# SixAxR.net
KiCad netlist of a schematic drawn in Altium Designer
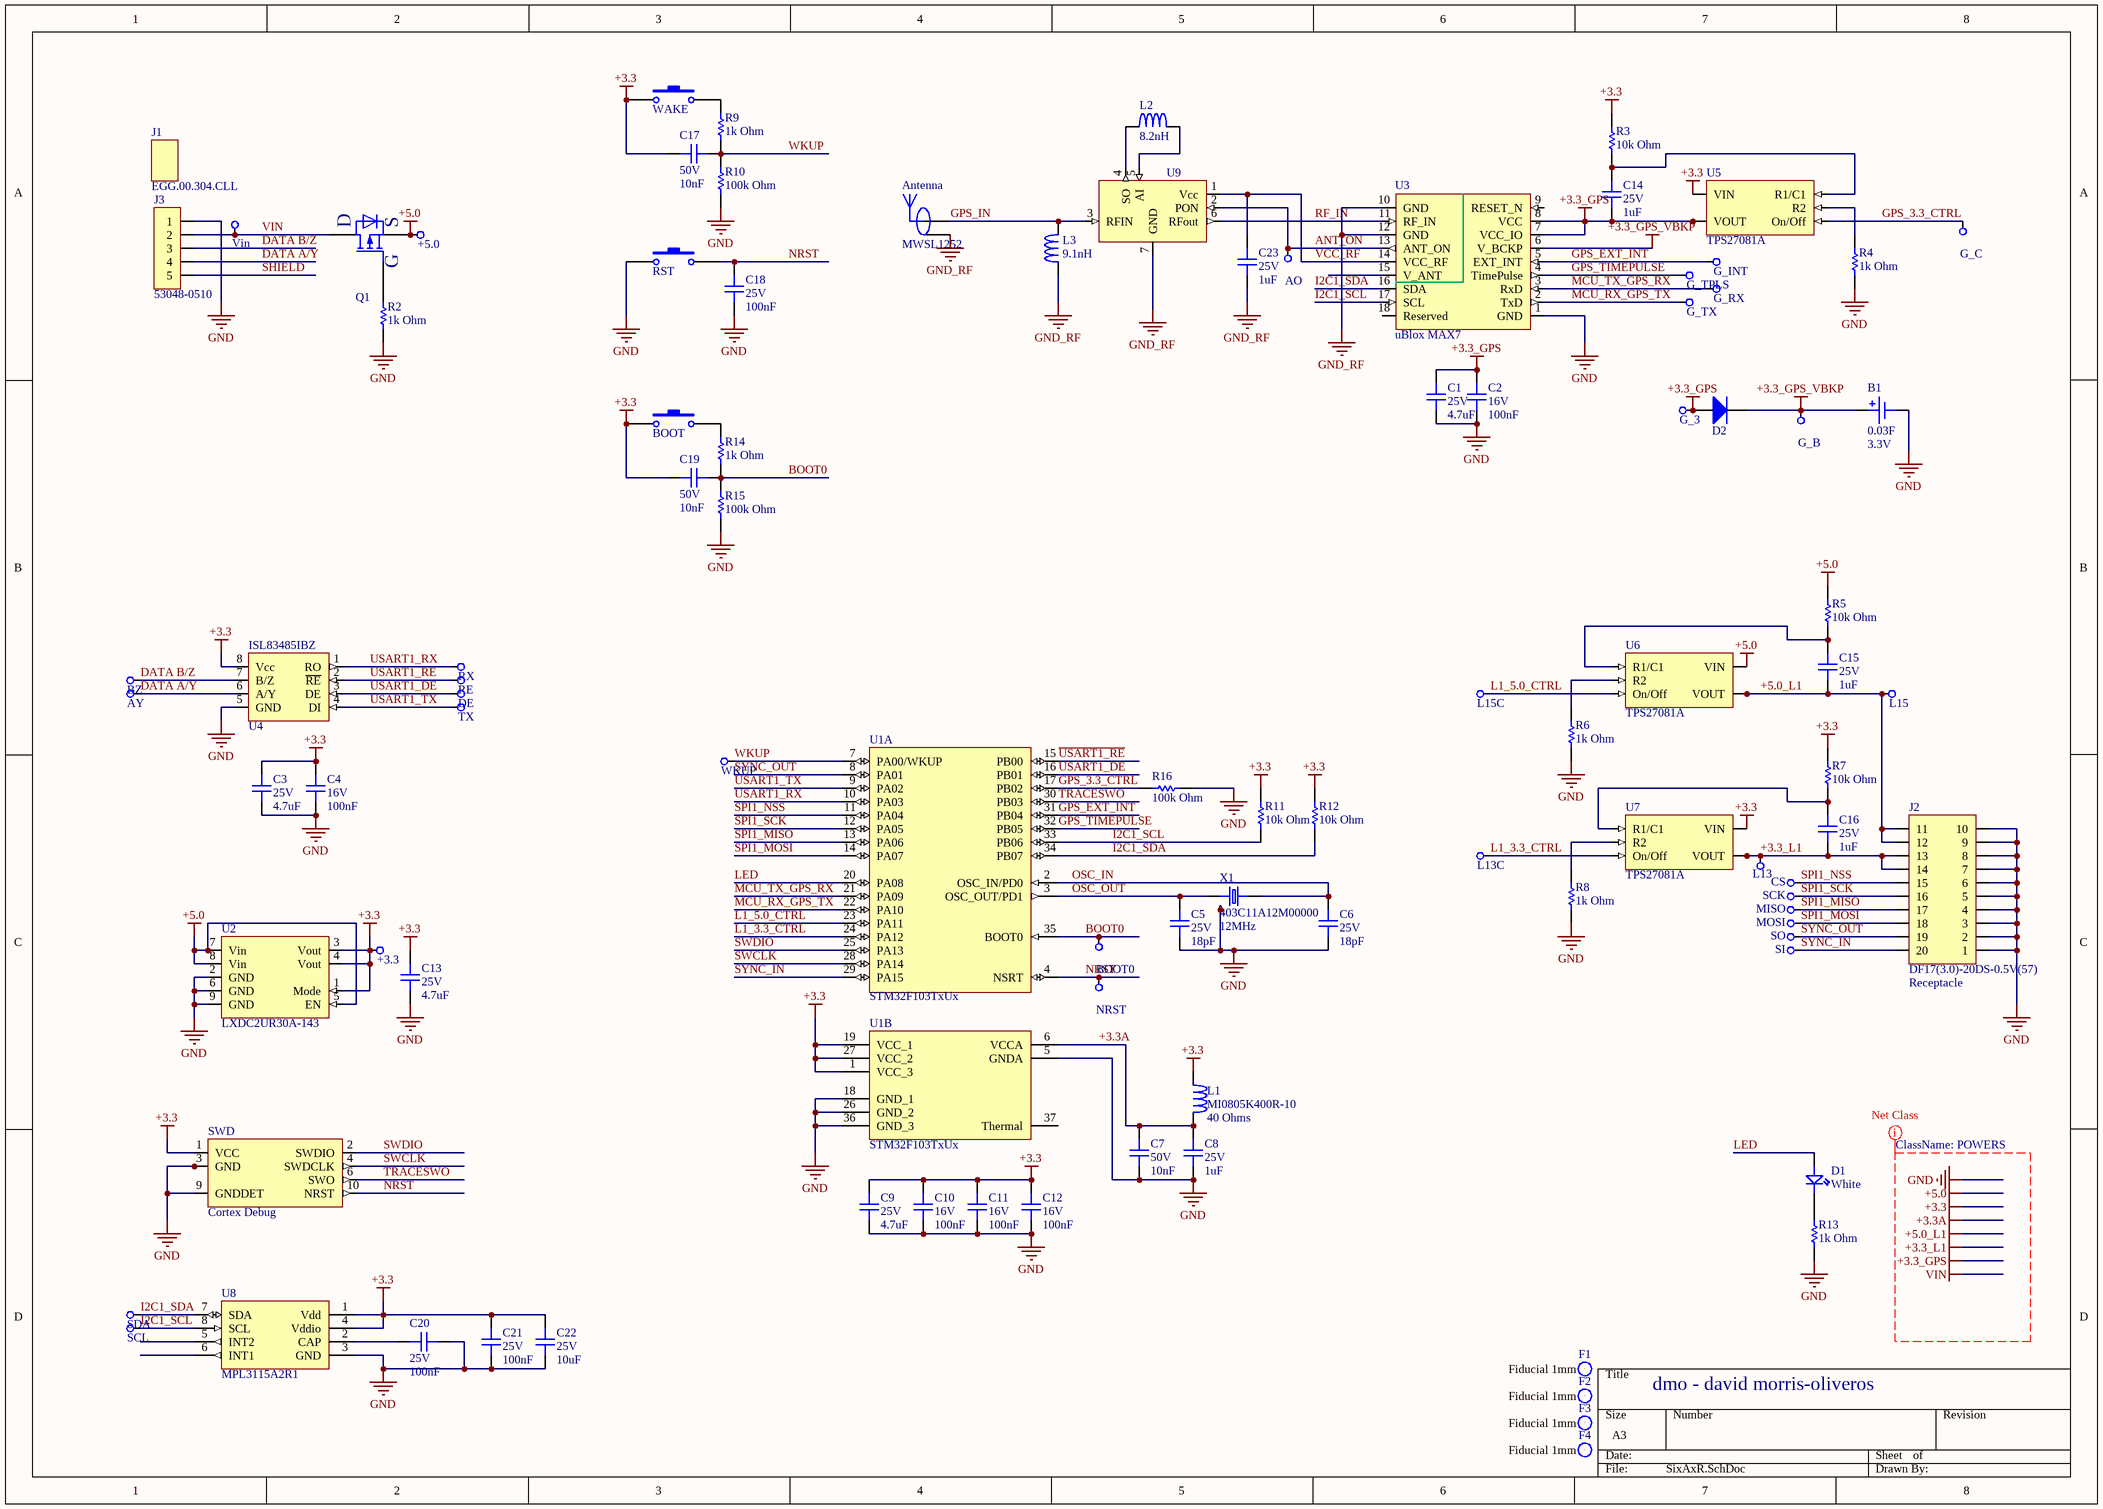
[diagram p0: SixAxR.SchDoc]

(export (version "E")
  (design (tool "Eeschema 10.0.6"))
  (components
    (comp (ref "+3.3")
      (value "TEST")
      (footprint "TEST_1.0mm, SMD")
      (libsource (lib "NaniBox_Conn") (part "TEST"))
    )
    (comp (ref "+5.0")
      (value "TEST")
      (footprint "TEST_1.0mm, SMD")
      (libsource (lib "NaniBox_Conn") (part "TEST"))
    )
    (comp (ref "Antenna")
      (value "MWSL1252")
      (footprint "MWSL1252 - Vertical - SMALLER")
      (description "GPS Antenna, Passive, SMD")
      (fields (field (name "MANUFACTURER") "Maruwa"))
      (libsource (lib "NaniBox_Conn") (part "MWSL1252"))
    )
    (comp (ref "AO")
      (value "TEST")
      (footprint "TEST_0.5mm, SMD")
      (libsource (lib "NaniBox_Conn") (part "TEST"))
    )
    (comp (ref "AY")
      (value "TEST")
      (footprint "TEST_0.5mm, SMD")
      (libsource (lib "NaniBox_Conn") (part "TEST"))
    )
    (comp (ref "B1")
      (value "0.03F")
      (footprint "PAS409HR-VE5R")
      (description "Super Cap, 3.3V, 0.03F")
      (fields
        (field (name "MANUFACTURER") "Taiyo Yuden")
        (field (name "MANUFACTURER PART NUMBER") "PAS409HR-VE5R")
        (field (name "VOLTAGE") "3.3V")
      )
      (libsource (lib "NaniBox") (part "PAS409HR-VE5R"))
    )
    (comp (ref "BOOT")
      (value "TL1015AF160QG")
      (footprint "TL1015AF160QG")
      (description "Switch, Tactile, SMD")
      (fields (field (name "MANUFACTURER") "E-Switch"))
      (libsource (lib "NaniBox") (part "TL1015AF160QG"))
    )
    (comp (ref "BOOT0")
      (value "TEST")
      (footprint "TEST_0.5mm, SMD")
      (libsource (lib "NaniBox_Conn") (part "TEST"))
    )
    (comp (ref "BZ")
      (value "TEST")
      (footprint "TEST_0.5mm, SMD")
      (libsource (lib "NaniBox_Conn") (part "TEST"))
    )
    (comp (ref "C1")
      (value "4.7uF")
      (footprint "CAP 0805")
      (description "MLCC, 4.7uF, 0805, 10%, 25V, X5R")
      (fields
        (field (name "MANUFACTURER") "Samsung")
        (field (name "MANUFACTURER PART NUMBER") "CL21A475KAQNNNE")
        (field (name "VOLTAGE RATING") "25V")
      )
      (libsource (lib "NaniBox") (part "CL21A475KAQNNNE"))
    )
    (comp (ref "C2")
      (value "100nF")
      (footprint "CAP 0402")
      (description "MLCC, 100nF, 0402, 10%, 16V, X7R")
      (fields
        (field (name "MANUFACTURER") "Samsung")
        (field (name "MANUFACTURER PART NUMBER") "CL05B104KO5NNNC")
        (field (name "VOLTAGE RATING") "16V")
      )
      (libsource (lib "NaniBox") (part "CL05B104KO5NNNC"))
    )
    (comp (ref "C3")
      (value "4.7uF")
      (footprint "CAP 0805")
      (description "MLCC, 4.7uF, 0805, 10%, 25V, X5R")
      (fields
        (field (name "MANUFACTURER") "Samsung")
        (field (name "MANUFACTURER PART NUMBER") "CL21A475KAQNNNE")
        (field (name "VOLTAGE RATING") "25V")
      )
      (libsource (lib "NaniBox") (part "CL21A475KAQNNNE"))
    )
    (comp (ref "C4")
      (value "100nF")
      (footprint "CAP 0402")
      (description "MLCC, 100nF, 0402, 10%, 16V, X7R")
      (fields
        (field (name "MANUFACTURER") "Samsung")
        (field (name "MANUFACTURER PART NUMBER") "CL05B104KO5NNNC")
        (field (name "VOLTAGE RATING") "16V")
      )
      (libsource (lib "NaniBox") (part "CL05B104KO5NNNC"))
    )
    (comp (ref "C5")
      (value "18pF")
      (footprint "CAP 0402")
      (description "MLCC, 18pF, 0402, 5%, 25V, C0G")
      (fields
        (field (name "MANUFACTURER") "muRata")
        (field (name "MANUFACTURER PART NUMBER") "GRM1555C1E180JA01D")
        (field (name "VOLTAGE RATING") "25V")
      )
      (libsource (lib "NaniBox") (part "GRM1555C1E180JA01D"))
    )
    (comp (ref "C6")
      (value "18pF")
      (footprint "CAP 0402")
      (description "MLCC, 18pF, 0402, 5%, 25V, C0G")
      (fields
        (field (name "MANUFACTURER") "muRata")
        (field (name "MANUFACTURER PART NUMBER") "GRM1555C1E180JA01D")
        (field (name "VOLTAGE RATING") "25V")
      )
      (libsource (lib "NaniBox") (part "GRM1555C1E180JA01D"))
    )
    (comp (ref "C7")
      (value "10nF")
      (footprint "CAP 0402")
      (description "MLCC, 10nF, 0402, 10%, 50V, X7R")
      (fields
        (field (name "MANUFACTURER") "Samsung")
        (field (name "MANUFACTURER PART NUMBER") "CL05B103KB5NNNC")
        (field (name "VOLTAGE RATING") "50V")
      )
      (libsource (lib "NaniBox") (part "CL05B103KB5NNNC"))
    )
    (comp (ref "C8")
      (value "1uF")
      (footprint "CAP 0603")
      (description "MLCC, 1uF, 0603, 10%, 25V")
      (fields
        (field (name "MANUFACTURER") "Taiyo Yuden")
        (field (name "MANUFACTURER PART NUMBER") "TMK107B7105KA-T")
        (field (name "VOLTAGE RATING") "25V")
      )
      (libsource (lib "NaniBox") (part "TMK107B7105KA-T"))
    )
    (comp (ref "C9")
      (value "4.7uF")
      (footprint "CAP 0805")
      (description "MLCC, 4.7uF, 0805, 10%, 25V, X5R")
      (fields
        (field (name "MANUFACTURER") "Samsung")
        (field (name "MANUFACTURER PART NUMBER") "CL21A475KAQNNNE")
        (field (name "VOLTAGE RATING") "25V")
      )
      (libsource (lib "NaniBox") (part "CL21A475KAQNNNE"))
    )
    (comp (ref "C10")
      (value "100nF")
      (footprint "CAP 0402")
      (description "MLCC, 100nF, 0402, 10%, 16V, X7R")
      (fields
        (field (name "MANUFACTURER") "Samsung")
        (field (name "MANUFACTURER PART NUMBER") "CL05B104KO5NNNC")
        (field (name "VOLTAGE RATING") "16V")
      )
      (libsource (lib "NaniBox") (part "CL05B104KO5NNNC"))
    )
    (comp (ref "C11")
      (value "100nF")
      (footprint "CAP 0402")
      (description "MLCC, 100nF, 0402, 10%, 16V, X7R")
      (fields
        (field (name "MANUFACTURER") "Samsung")
        (field (name "MANUFACTURER PART NUMBER") "CL05B104KO5NNNC")
        (field (name "VOLTAGE RATING") "16V")
      )
      (libsource (lib "NaniBox") (part "CL05B104KO5NNNC"))
    )
    (comp (ref "C12")
      (value "100nF")
      (footprint "CAP 0402")
      (description "MLCC, 100nF, 0402, 10%, 16V, X7R")
      (fields
        (field (name "MANUFACTURER") "Samsung")
        (field (name "MANUFACTURER PART NUMBER") "CL05B104KO5NNNC")
        (field (name "VOLTAGE RATING") "16V")
      )
      (libsource (lib "NaniBox") (part "CL05B104KO5NNNC"))
    )
    (comp (ref "C13")
      (value "4.7uF")
      (footprint "CAP 0805")
      (description "MLCC, 4.7uF, 0805, 10%, 25V, X5R")
      (fields
        (field (name "MANUFACTURER") "Samsung")
        (field (name "MANUFACTURER PART NUMBER") "CL21A475KAQNNNE")
        (field (name "VOLTAGE RATING") "25V")
      )
      (libsource (lib "NaniBox") (part "CL21A475KAQNNNE"))
    )
    (comp (ref "C14")
      (value "1uF")
      (footprint "CAP 0603")
      (description "MLCC, 1uF, 0603, 10%, 25V, X5R")
      (fields
        (field (name "MANUFACTURER") "Samsung")
        (field (name "MANUFACTURER PART NUMBER") "CL10A105KA8NNNC")
        (field (name "VOLTAGE RATING") "25V")
      )
      (libsource (lib "NaniBox") (part "CL10A105KA8NNNC"))
    )
    (comp (ref "C15")
      (value "1uF")
      (footprint "CAP 0603")
      (description "MLCC, 1uF, 0603, 10%, 25V, X5R")
      (fields
        (field (name "MANUFACTURER") "Samsung")
        (field (name "MANUFACTURER PART NUMBER") "CL10A105KA8NNNC")
        (field (name "VOLTAGE RATING") "25V")
      )
      (libsource (lib "NaniBox") (part "CL10A105KA8NNNC"))
    )
    (comp (ref "C16")
      (value "1uF")
      (footprint "CAP 0603")
      (description "MLCC, 1uF, 0603, 10%, 25V, X5R")
      (fields
        (field (name "MANUFACTURER") "Samsung")
        (field (name "MANUFACTURER PART NUMBER") "CL10A105KA8NNNC")
        (field (name "VOLTAGE RATING") "25V")
      )
      (libsource (lib "NaniBox") (part "CL10A105KA8NNNC"))
    )
    (comp (ref "C17")
      (value "10nF")
      (footprint "CAP 0402")
      (description "MLCC, 10nF, 0402, 10%, 50V, X7R")
      (fields
        (field (name "MANUFACTURER") "Samsung")
        (field (name "MANUFACTURER PART NUMBER") "CL05B103KB5NNNC")
        (field (name "VOLTAGE RATING") "50V")
      )
      (libsource (lib "NaniBox") (part "CL05B103KB5NNNC"))
    )
    (comp (ref "C18")
      (value "100nF")
      (footprint "CAP 0402")
      (description "MLCC, 100nF, 0402, 10%, 25V, X5R")
      (fields
        (field (name "MANUFACTURER") "Samsung")
        (field (name "MANUFACTURER PART NUMBER") "CL05A104KA5NNNC")
        (field (name "VOLTAGE RATING") "25V")
      )
      (libsource (lib "NaniBox") (part "CL05A104KA5NNNC"))
    )
    (comp (ref "C19")
      (value "10nF")
      (footprint "CAP 0402")
      (description "MLCC, 10nF, 0402, 10%, 50V, X7R")
      (fields
        (field (name "MANUFACTURER") "Samsung")
        (field (name "MANUFACTURER PART NUMBER") "CL05B103KB5NNNC")
        (field (name "VOLTAGE RATING") "50V")
      )
      (libsource (lib "NaniBox") (part "CL05B103KB5NNNC"))
    )
    (comp (ref "C20")
      (value "100nF")
      (footprint "CAP 0402")
      (description "MLCC, 100nF, 0402, 10%, 25V, X5R")
      (fields
        (field (name "MANUFACTURER") "Samsung")
        (field (name "MANUFACTURER PART NUMBER") "CL05A104KA5NNNC")
        (field (name "VOLTAGE RATING") "25V")
      )
      (libsource (lib "NaniBox") (part "CL05A104KA5NNNC"))
    )
    (comp (ref "C21")
      (value "100nF")
      (footprint "CAP 0402")
      (description "MLCC, 100nF, 0402, 10%, 25V, X5R")
      (fields
        (field (name "MANUFACTURER") "Samsung")
        (field (name "MANUFACTURER PART NUMBER") "CL05A104KA5NNNC")
        (field (name "VOLTAGE RATING") "25V")
      )
      (libsource (lib "NaniBox") (part "CL05A104KA5NNNC"))
    )
    (comp (ref "C22")
      (value "10uF")
      (footprint "CAP 0805")
      (description "MLCC, 10uF, 0805, 10%, 25V, X5R")
      (fields
        (field (name "MANUFACTURER") "Samsung")
        (field (name "MANUFACTURER PART NUMBER") "CL21A106KAYNNNE")
        (field (name "VOLTAGE RATING") "25V")
      )
      (libsource (lib "NaniBox") (part "CL21A106KAYNNNE"))
    )
    (comp (ref "C23")
      (value "1uF")
      (footprint "CAP 0603")
      (description "MLCC, 1uF, 0603, 10%, 25V, X5R")
      (fields
        (field (name "MANUFACTURER") "Samsung")
        (field (name "MANUFACTURER PART NUMBER") "CL10A105KA8NNNC")
        (field (name "VOLTAGE RATING") "25V")
      )
      (libsource (lib "NaniBox") (part "CL10A105KA8NNNC"))
    )
    (comp (ref "CS")
      (value "TEST")
      (footprint "TEST_0.5mm, SMD")
      (libsource (lib "NaniBox_Conn") (part "TEST"))
    )
    (comp (ref "D1")
      (value "White")
      (footprint "LED 0603")
      (description "LED, White, 0603")
      (fields (field (name "MANUFACTURER PART NUMBER") "1608SWD-04"))
      (libsource (lib "NaniBox") (part "1608SWD-04"))
    )
    (comp (ref "D2")
      (value "CDSQR400B")
      (footprint "SOD-923F")
      (description "DIODE, Switching, Low Leakage, 90V, 100mA")
      (fields (field (name "MANUFACTURER") "Comchip Technology"))
      (libsource (lib "NaniBox") (part "CDSQR400B"))
    )
    (comp (ref "DE")
      (value "TEST")
      (footprint "TEST_0.5mm, SMD")
      (libsource (lib "NaniBox_Conn") (part "TEST"))
    )
    (comp (ref "F1")
      (value "~")
      (footprint "Fiducial_1mm")
      (libsource (lib "NaniBox_Conn") (part "Fiducial 1mm"))
    )
    (comp (ref "F2")
      (value "~")
      (footprint "Fiducial_1mm")
      (libsource (lib "NaniBox_Conn") (part "Fiducial 1mm"))
    )
    (comp (ref "F3")
      (value "~")
      (footprint "Fiducial_1mm")
      (libsource (lib "NaniBox_Conn") (part "Fiducial 1mm"))
    )
    (comp (ref "F4")
      (value "~")
      (footprint "Fiducial_1mm")
      (libsource (lib "NaniBox_Conn") (part "Fiducial 1mm"))
    )
    (comp (ref "G_3")
      (value "TEST")
      (footprint "TEST_0.5mm, SMD")
      (libsource (lib "NaniBox_Conn") (part "TEST"))
    )
    (comp (ref "G_B")
      (value "TEST")
      (footprint "TEST_0.5mm, SMD")
      (libsource (lib "NaniBox_Conn") (part "TEST"))
    )
    (comp (ref "G_C")
      (value "TEST")
      (footprint "TEST_0.5mm, SMD")
      (libsource (lib "NaniBox_Conn") (part "TEST"))
    )
    (comp (ref "G_INT")
      (value "TEST")
      (footprint "TEST_0.5mm, SMD")
      (libsource (lib "NaniBox_Conn") (part "TEST"))
    )
    (comp (ref "G_RX")
      (value "TEST")
      (footprint "TEST_0.5mm, SMD")
      (libsource (lib "NaniBox_Conn") (part "TEST"))
    )
    (comp (ref "G_TPLS")
      (value "TEST")
      (footprint "TEST_0.5mm, SMD")
      (libsource (lib "NaniBox_Conn") (part "TEST"))
    )
    (comp (ref "G_TX")
      (value "TEST")
      (footprint "TEST_0.5mm, SMD")
      (libsource (lib "NaniBox_Conn") (part "TEST"))
    )
    (comp (ref "J1")
      (value "EGG.00.304.CLL")
      (footprint "EGG.00.304.CLL")
      (description "LEMO 00, 4-pin")
      (libsource (lib "NaniBox") (part "EGG.00.304.CLL"))
    )
    (comp (ref "J2")
      (value "DF17(3.0)-20DS-0.5V(57)")
      (footprint "DF17(3.0)-20DS-0.5V(57)")
      (description "Conn, B2B, 20 Pos, RCPT")
      (fields (field (name "MANUFACTURER") "Hirose") (field (name "TYPE") "Receptacle"))
      (libsource (lib "NaniBox") (part "DF17(3.0)-20DS-0.5V(57)"))
    )
    (comp (ref "J3")
      (value "53048-0510")
      (footprint "PicoBlade, 53048-0510")
      (description "PicoBlade, Header, R/A, PTH, 5 Pos, 1.25mm Pitch")
      (fields (field (name "MANUFACTURER") "Molex"))
      (libsource (lib "NaniBox_Conn") (part "53048-0510"))
    )
    (comp (ref "L1")
      (value "MI0805K400R-10")
      (footprint "IND 0805")
      (description "IND, EMI, 40Ohm, 100MHz, 1.5A, 0805")
      (fields (field (name "MANUFACTURER") "Laird") (field (name "IMPEDENCE") "40 Ohms"))
      (libsource (lib "NaniBox") (part "MI0805K400R-10"))
    )
    (comp (ref "L2")
      (value "8.2nH")
      (footprint "IND 0402")
      (description "IND, 8.2nH, 5%, 100MHz")
      (fields
        (field (name "MANUFACTURER") "Murata Electronics")
        (field (name "MANUFACTURER PART NUMBER") "LQW15AN8N2J00D")
      )
      (libsource (lib "NaniBox") (part "LQW15AN8N2J00D"))
    )
    (comp (ref "L3")
      (value "9.1nH")
      (footprint "IND 0402")
      (description "IND, 9.1nH, 5%, 100MHz")
      (fields
        (field (name "MANUFACTURER") "Murata Electronics")
        (field (name "MANUFACTURER PART NUMBER") "LQW15AN9N1J00D")
      )
      (libsource (lib "NaniBox") (part "LQW15AN9N1J00D"))
    )
    (comp (ref "L13")
      (value "TEST")
      (footprint "TEST_0.5mm, SMD")
      (libsource (lib "NaniBox_Conn") (part "TEST"))
    )
    (comp (ref "L13C")
      (value "TEST")
      (footprint "TEST_0.5mm, SMD")
      (libsource (lib "NaniBox_Conn") (part "TEST"))
    )
    (comp (ref "L15")
      (value "TEST")
      (footprint "TEST_0.5mm, SMD")
      (libsource (lib "NaniBox_Conn") (part "TEST"))
    )
    (comp (ref "L15C")
      (value "TEST")
      (footprint "TEST_0.5mm, SMD")
      (libsource (lib "NaniBox_Conn") (part "TEST"))
    )
    (comp (ref "MISO")
      (value "TEST")
      (footprint "TEST_0.5mm, SMD")
      (libsource (lib "NaniBox_Conn") (part "TEST"))
    )
    (comp (ref "MOSI")
      (value "TEST")
      (footprint "TEST_0.5mm, SMD")
      (libsource (lib "NaniBox_Conn") (part "TEST"))
    )
    (comp (ref "NRST")
      (value "TEST")
      (footprint "TEST_0.5mm, SMD")
      (libsource (lib "NaniBox_Conn") (part "TEST"))
    )
    (comp (ref "Q1")
      (value "PMV48XP,215")
      (footprint "SOT23-3")
      (description "MOSFET P-CH -20 V -3.5 A, SOT23-3")
      (fields (field (name "MANUFACTURER") "NXP"))
      (libsource (lib "NaniBox") (part "PMV48XP,215"))
    )
    (comp (ref "R2")
      (value "1k Ohm")
      (footprint "RES 0402")
      (description "RES, 0402, 1k, 1%")
      (fields (field (name "TOLERANCE") "1%") (field (name "MANUFACTURER") "Yageo"))
      (libsource (lib "NaniBox") (part "P311-1.00KLRTR-ND"))
    )
    (comp (ref "R3")
      (value "10k Ohm")
      (footprint "RES 0402")
      (description "RES, 0402, 10k, 1%")
      (fields (field (name "TOLERANCE") "1%") (field (name "MANUFACTURER") "Yageo"))
      (libsource (lib "NaniBox") (part "P311-10.0KLRTR-ND"))
    )
    (comp (ref "R4")
      (value "1k Ohm")
      (footprint "RES 0402")
      (description "RES, 0402, 1k, 1%")
      (fields (field (name "TOLERANCE") "1%") (field (name "MANUFACTURER") "Yageo"))
      (libsource (lib "NaniBox") (part "P311-1.00KLRTR-ND"))
    )
    (comp (ref "R5")
      (value "10k Ohm")
      (footprint "RES 0402")
      (description "RES, 0402, 10k, 1%")
      (fields (field (name "TOLERANCE") "1%") (field (name "MANUFACTURER") "Yageo"))
      (libsource (lib "NaniBox") (part "P311-10.0KLRTR-ND"))
    )
    (comp (ref "R6")
      (value "1k Ohm")
      (footprint "RES 0402")
      (description "RES, 0402, 1k, 1%")
      (fields (field (name "TOLERANCE") "1%") (field (name "MANUFACTURER") "Yageo"))
      (libsource (lib "NaniBox") (part "P311-1.00KLRTR-ND"))
    )
    (comp (ref "R7")
      (value "10k Ohm")
      (footprint "RES 0402")
      (description "RES, 0402, 10k, 1%")
      (fields (field (name "TOLERANCE") "1%") (field (name "MANUFACTURER") "Yageo"))
      (libsource (lib "NaniBox") (part "P311-10.0KLRTR-ND"))
    )
    (comp (ref "R8")
      (value "1k Ohm")
      (footprint "RES 0402")
      (description "RES, 0402, 1k, 1%")
      (fields (field (name "TOLERANCE") "1%") (field (name "MANUFACTURER") "Yageo"))
      (libsource (lib "NaniBox") (part "P311-1.00KLRTR-ND"))
    )
    (comp (ref "R9")
      (value "1k Ohm")
      (footprint "RES 0402")
      (description "RES, 0402, 1k, 1%")
      (fields (field (name "TOLERANCE") "1%") (field (name "MANUFACTURER") "Yageo"))
      (libsource (lib "NaniBox") (part "P311-1.00KLRTR-ND"))
    )
    (comp (ref "R10")
      (value "100k Ohm")
      (footprint "RES 0402")
      (description "RES, 0402, 100k, 1%")
      (fields (field (name "TOLERANCE") "1%") (field (name "MANUFACTURER") "Yageo"))
      (libsource (lib "NaniBox") (part "P311-100KLRTR-ND"))
    )
    (comp (ref "R11")
      (value "10k Ohm")
      (footprint "RES 0402")
      (description "RES, 0402, 10k, 1%")
      (fields (field (name "TOLERANCE") "1%") (field (name "MANUFACTURER") "Yageo"))
      (libsource (lib "NaniBox") (part "P311-10.0KLRTR-ND"))
    )
    (comp (ref "R12")
      (value "10k Ohm")
      (footprint "RES 0402")
      (description "RES, 0402, 10k, 1%")
      (fields (field (name "TOLERANCE") "1%") (field (name "MANUFACTURER") "Yageo"))
      (libsource (lib "NaniBox") (part "P311-10.0KLRTR-ND"))
    )
    (comp (ref "R13")
      (value "1k Ohm")
      (footprint "RES 0402")
      (description "RES, 0402, 1k, 1%")
      (fields (field (name "TOLERANCE") "1%") (field (name "MANUFACTURER") "Yageo"))
      (libsource (lib "NaniBox") (part "P311-1.00KLRTR-ND"))
    )
    (comp (ref "R14")
      (value "1k Ohm")
      (footprint "RES 0402")
      (description "RES, 0402, 1k, 1%")
      (fields (field (name "TOLERANCE") "1%") (field (name "MANUFACTURER") "Yageo"))
      (libsource (lib "NaniBox") (part "P311-1.00KLRTR-ND"))
    )
    (comp (ref "R15")
      (value "100k Ohm")
      (footprint "RES 0402")
      (description "RES, 0402, 100k, 1%")
      (fields (field (name "TOLERANCE") "1%") (field (name "MANUFACTURER") "Yageo"))
      (libsource (lib "NaniBox") (part "P311-100KLRTR-ND"))
    )
    (comp (ref "R16")
      (value "100k Ohm")
      (footprint "RES 0402")
      (description "RES, 0402, 100k, 1%")
      (fields (field (name "TOLERANCE") "1%") (field (name "MANUFACTURER") "Yageo"))
      (libsource (lib "NaniBox") (part "P311-100KLRTR-ND"))
    )
    (comp (ref "RE")
      (value "TEST")
      (footprint "TEST_0.5mm, SMD")
      (libsource (lib "NaniBox_Conn") (part "TEST"))
    )
    (comp (ref "RST")
      (value "TL1015AF160QG")
      (footprint "TL1015AF160QG")
      (description "Switch, Tactile, SMD")
      (fields (field (name "MANUFACTURER") "E-Switch"))
      (libsource (lib "NaniBox") (part "TL1015AF160QG"))
    )
    (comp (ref "RX")
      (value "TEST")
      (footprint "TEST_0.5mm, SMD")
      (libsource (lib "NaniBox_Conn") (part "TEST"))
    )
    (comp (ref "SCK")
      (value "TEST")
      (footprint "TEST_0.5mm, SMD")
      (libsource (lib "NaniBox_Conn") (part "TEST"))
    )
    (comp (ref "SCL")
      (value "TEST")
      (footprint "TEST_0.5mm, SMD")
      (libsource (lib "NaniBox_Conn") (part "TEST"))
    )
    (comp (ref "SDA")
      (value "TEST")
      (footprint "TEST_0.5mm, SMD")
      (libsource (lib "NaniBox_Conn") (part "TEST"))
    )
    (comp (ref "SI")
      (value "TEST")
      (footprint "TEST_0.5mm, SMD")
      (libsource (lib "NaniBox_Conn") (part "TEST"))
    )
    (comp (ref "SO")
      (value "TEST")
      (footprint "TEST_0.5mm, SMD")
      (libsource (lib "NaniBox_Conn") (part "TEST"))
    )
    (comp (ref "SWD")
      (value "CORTEX_DEBUG")
      (footprint "H_05x02 - 1.27mm")
      (description "Cortex Debug")
      (fields (field (name "MANUFACTURER PART NUMBER") "Cortex Debug"))
      (libsource (lib "NaniBox") (part "CORTEX_DEBUG"))
    )
    (comp (ref "TX")
      (value "TEST")
      (footprint "TEST_0.5mm, SMD")
      (libsource (lib "NaniBox_Conn") (part "TEST"))
    )
    (comp (ref "U1")
      (value "STM32F103TxUx")
      (footprint "QFN36 - 0.5mm - NO THERMAL VIAS")
      (description "MCU, ARM-based 32-bit MCU with 64  or 128 KB Flash, USB, CAN, 7 timers, 2 ADCs, 9 com. interfaces")
      (libsource (lib "NaniBox") (part "STM32F103TxUx"))
    )
    (comp (ref "U2")
      (value "LXDC2UR30A-143")
      (footprint "BGA - 9 - LXDC2UR")
      (description "DC-DC 3.0Vout 600mA 2.5x2.3mm uDCDC")
      (libsource (lib "NaniBox") (part "LXDC2UR30A-143"))
    )
    (comp (ref "U3")
      (value "uBlox MAX7")
      (footprint "uBlox MAX7")
      (description "GPS, u-blox 7 GPS/GNSS module")
      (libsource (lib "NaniBox") (part "uBlox MAX7"))
    )
    (comp (ref "U4")
      (value "ISL83485IBZ")
      (footprint "SOIC8")
      (description "RS-422/RS-485, 3.3V, HalfDuplex, TRN 1TX/1RX, W/SHTDN")
      (fields (field (name "MANUFACTURER") "Intersil"))
      (libsource (lib "NaniBox") (part "ISL83485IBZ"))
    )
    (comp (ref "U5")
      (value "TPS27081ADDCR")
      (footprint "SOT23-6")
      (description "High Side Load Switch PFET 1.2V-8V 3A")
      (fields
        (field (name "MANUFACTURER") "TI")
        (field (name "MANUFACTURER PART NUMBER - SIMPLE") "TPS27081A")
      )
      (libsource (lib "") (part "TPS27081ADDCR_1"))
    )
    (comp (ref "U6")
      (value "TPS27081ADDCR")
      (footprint "SOT23-6")
      (description "High Side Load Switch PFET 1.2V-8V 3A")
      (fields
        (field (name "MANUFACTURER") "TI")
        (field (name "MANUFACTURER PART NUMBER - SIMPLE") "TPS27081A")
      )
      (libsource (lib "NaniBox") (part "TPS27081ADDCR"))
    )
    (comp (ref "U7")
      (value "TPS27081ADDCR")
      (footprint "SOT23-6")
      (description "High Side Load Switch PFET 1.2V-8V 3A")
      (fields
        (field (name "MANUFACTURER") "TI")
        (field (name "MANUFACTURER PART NUMBER - SIMPLE") "TPS27081A")
      )
      (libsource (lib "NaniBox") (part "TPS27081ADDCR"))
    )
    (comp (ref "U8")
      (value "MPL3115A2R1")
      (footprint "MPL3115A2R1")
      (description "Barometric Pressure Sensor, SMD")
      (fields (field (name "MANUFACTURER") "Freescale"))
      (libsource (lib "NaniBox") (part "MPL3115A2R1"))
    )
    (comp (ref "U9")
      (value "BGM1043N7")
      (footprint "TSNP-7-10")
      (description "RF, LNA, GPS")
      (fields (field (name "MANUFACTURER") "Infineon"))
      (libsource (lib "NaniBox") (part "BGM1043N7"))
    )
    (comp (ref "Vin")
      (value "TEST")
      (footprint "TEST_1.0mm, SMD")
      (libsource (lib "NaniBox_Conn") (part "TEST"))
    )
    (comp (ref "WAKE")
      (value "EVQ-P44B3M")
      (footprint "EVQ-P44B3M")
      (description "Switch, Tactile, Right Angle, Mid-Plane Mount,, SMD")
      (fields (field (name "MANUFACTURER") "E-Switch"))
      (libsource (lib "NaniBox") (part "EVQ-P44B3M"))
    )
    (comp (ref "WKUP")
      (value "TEST")
      (footprint "TEST_0.5mm, SMD")
      (libsource (lib "NaniBox_Conn") (part "TEST"))
    )
    (comp (ref "X1")
      (value "403C11A12M00000")
      (footprint "XTAL_3.2x2.5")
      (description "Crystal 12MHz 10pF 10ppm 3.2x2.5mm")
      (fields (field (name "FREQUENCY") "12MHz") (field (name "MANUFACTURER") "CTS Electronic Components"))
      (libsource (lib "NaniBox") (part "403C11A12M00000"))
    )
  )
  (nets
    (net (code "1") (name "+3.3") (class "Default")
      (node (ref "+3.3") (pin "0") (pinfunction "0_0") (pintype "passive"))
      (node (ref "BOOT") (pin "1") (pinfunction "1_1") (pintype "passive"))
      (node (ref "C10") (pin "2") (pinfunction "2_2") (pintype "passive"))
      (node (ref "C11") (pin "2") (pinfunction "2_2") (pintype "passive"))
      (node (ref "C12") (pin "2") (pinfunction "2_2") (pintype "passive"))
      (node (ref "C13") (pin "2") (pinfunction "2_2") (pintype "passive"))
      (node (ref "C17") (pin "1") (pinfunction "1_1") (pintype "passive"))
      (node (ref "C19") (pin "1") (pinfunction "1_1") (pintype "passive"))
      (node (ref "C21") (pin "2") (pinfunction "2_2") (pintype "passive"))
      (node (ref "C22") (pin "2") (pinfunction "2_2") (pintype "passive"))
      (node (ref "C3") (pin "2") (pinfunction "2_2") (pintype "passive"))
      (node (ref "C4") (pin "2") (pinfunction "2_2") (pintype "passive"))
      (node (ref "C9") (pin "2") (pinfunction "2_2") (pintype "passive"))
      (node (ref "L1") (pin "1") (pinfunction "1_1") (pintype "passive"))
      (node (ref "R11") (pin "2") (pinfunction "2_2") (pintype "passive"))
      (node (ref "R12") (pin "2") (pinfunction "2_2") (pintype "passive"))
      (node (ref "R3") (pin "2") (pinfunction "2_2") (pintype "passive"))
      (node (ref "R7") (pin "2") (pinfunction "2_2") (pintype "passive"))
      (node (ref "SWD") (pin "1") (pinfunction "VCC_1") (pintype "passive"))
      (node (ref "U1") (pin "1") (pinfunction "VCC_3_1") (pintype "power_in"))
      (node (ref "U1") (pin "19") (pinfunction "VCC_1_19") (pintype "power_in"))
      (node (ref "U1") (pin "27") (pinfunction "VCC_2_27") (pintype "power_in"))
      (node (ref "U2") (pin "1") (pinfunction "Mode_1") (pintype "input"))
      (node (ref "U2") (pin "3") (pinfunction "Vout_3") (pintype "power_in"))
      (node (ref "U2") (pin "4") (pinfunction "Vout_4") (pintype "power_in"))
      (node (ref "U4") (pin "8") (pinfunction "Vcc_8") (pintype "power_in"))
      (node (ref "U5") (pin "4") (pinfunction "VIN_4") (pintype "power_in"))
      (node (ref "U7") (pin "4") (pinfunction "VIN_4") (pintype "power_in"))
      (node (ref "U8") (pin "1") (pinfunction "Vdd_1") (pintype "power_in"))
      (node (ref "U8") (pin "4") (pinfunction "Vddio_4") (pintype "power_in"))
      (node (ref "WAKE") (pin "1") (pinfunction "1_1") (pintype "passive"))
    )
    (net (code "2") (name "+3.3A") (class "Default")
      (node (ref "C7") (pin "2") (pinfunction "2_2") (pintype "passive"))
      (node (ref "C8") (pin "2") (pinfunction "2_2") (pintype "passive"))
      (node (ref "L1") (pin "2") (pinfunction "2_2") (pintype "passive"))
      (node (ref "U1") (pin "6") (pinfunction "VCCA_6") (pintype "power_in"))
    )
    (net (code "3") (name "+3.3_GPS") (class "Default")
      (node (ref "C1") (pin "2") (pinfunction "2_2") (pintype "passive"))
      (node (ref "C14") (pin "1") (pinfunction "1_1") (pintype "passive"))
      (node (ref "C2") (pin "2") (pinfunction "2_2") (pintype "passive"))
      (node (ref "D2") (pin "1") (pinfunction "A_1") (pintype "passive"))
      (node (ref "G_3") (pin "0") (pinfunction "0_0") (pintype "passive"))
      (node (ref "U3") (pin "7") (pinfunction "VCC_IO_7") (pintype "power_in"))
      (node (ref "U3") (pin "8") (pinfunction "VCC_8") (pintype "power_in"))
      (node (ref "U5") (pin "2") (pinfunction "VOUT_2") (pintype "power_in"))
      (node (ref "U5") (pin "3") (pinfunction "VOUT_3") (pintype "power_in"))
    )
    (net (code "4") (name "+3.3_GPS_VBKP") (class "Default")
      (node (ref "B1") (pin "+") (pinfunction "+_+") (pintype "power_in"))
      (node (ref "D2") (pin "2") (pinfunction "K_2") (pintype "passive"))
      (node (ref "G_B") (pin "0") (pinfunction "0_0") (pintype "passive"))
      (node (ref "U3") (pin "6") (pinfunction "V_BCKP_6") (pintype "power_in"))
    )
    (net (code "5") (name "+3.3_L1") (class "Default")
      (node (ref "C16") (pin "1") (pinfunction "1_1") (pintype "passive"))
      (node (ref "J2") (pin "13") (pinfunction "13_13") (pintype "passive"))
      (node (ref "J2") (pin "14") (pinfunction "14_14") (pintype "passive"))
      (node (ref "L13") (pin "0") (pinfunction "0_0") (pintype "passive"))
      (node (ref "U7") (pin "2") (pinfunction "VOUT_2") (pintype "power_in"))
      (node (ref "U7") (pin "3") (pinfunction "VOUT_3") (pintype "power_in"))
    )
    (net (code "6") (name "+5.0") (class "Default")
      (node (ref "+5.0") (pin "0") (pinfunction "0_0") (pintype "passive"))
      (node (ref "Q1") (pin "2") (pinfunction "S_2") (pintype "passive"))
      (node (ref "R5") (pin "2") (pinfunction "2_2") (pintype "passive"))
      (node (ref "U2") (pin "5") (pinfunction "EN_5") (pintype "input"))
      (node (ref "U2") (pin "7") (pinfunction "Vin_7") (pintype "power_in"))
      (node (ref "U2") (pin "8") (pinfunction "Vin_8") (pintype "power_in"))
      (node (ref "U6") (pin "4") (pinfunction "VIN_4") (pintype "power_in"))
    )
    (net (code "7") (name "+5.0_L1") (class "Default")
      (node (ref "C15") (pin "1") (pinfunction "1_1") (pintype "passive"))
      (node (ref "J2") (pin "11") (pinfunction "11_11") (pintype "passive"))
      (node (ref "J2") (pin "12") (pinfunction "12_12") (pintype "passive"))
      (node (ref "L15") (pin "0") (pinfunction "0_0") (pintype "passive"))
      (node (ref "U6") (pin "2") (pinfunction "VOUT_2") (pintype "power_in"))
      (node (ref "U6") (pin "3") (pinfunction "VOUT_3") (pintype "power_in"))
    )
    (net (code "8") (name "/ANT_ON") (class "Default")
      (node (ref "AO") (pin "0") (pinfunction "0_0") (pintype "passive"))
      (node (ref "U3") (pin "13") (pinfunction "ANT_ON_13") (pintype "output"))
      (node (ref "U9") (pin "2") (pinfunction "PON_2") (pintype "input"))
    )
    (net (code "9") (name "/BOOT0") (class "Default")
      (node (ref "BOOT0") (pin "0") (pinfunction "0_0") (pintype "passive"))
      (node (ref "C19") (pin "2") (pinfunction "2_2") (pintype "passive"))
      (node (ref "R14") (pin "1") (pinfunction "1_1") (pintype "passive"))
      (node (ref "R15") (pin "2") (pinfunction "2_2") (pintype "passive"))
      (node (ref "U1") (pin "35") (pinfunction "BOOT0_35") (pintype "input"))
    )
    (net (code "10") (name "/DATA A{slash}Y") (class "Default")
      (node (ref "AY") (pin "0") (pinfunction "0_0") (pintype "passive"))
      (node (ref "J3") (pin "4") (pinfunction "4_4") (pintype "passive"))
      (node (ref "U4") (pin "6") (pinfunction "A/Y_6") (pintype "bidirectional"))
    )
    (net (code "11") (name "/DATA B{slash}Z") (class "Default")
      (node (ref "BZ") (pin "0") (pinfunction "0_0") (pintype "passive"))
      (node (ref "J3") (pin "3") (pinfunction "3_3") (pintype "passive"))
      (node (ref "U4") (pin "7") (pinfunction "B/Z_7") (pintype "bidirectional"))
    )
    (net (code "12") (name "/GPS_3.3_CTRL") (class "Default")
      (node (ref "G_C") (pin "0") (pinfunction "0_0") (pintype "passive"))
      (node (ref "R16") (pin "1") (pinfunction "1_1") (pintype "passive"))
      (node (ref "U1") (pin "17") (pinfunction "PB02_17") (pintype "bidirectional"))
      (node (ref "U5") (pin "5") (pinfunction "On/Off_5") (pintype "input"))
    )
    (net (code "13") (name "/GPS_EXT_INT") (class "Default")
      (node (ref "G_INT") (pin "0") (pinfunction "0_0") (pintype "passive"))
      (node (ref "U1") (pin "31") (pinfunction "PB04_31") (pintype "bidirectional"))
      (node (ref "U3") (pin "5") (pinfunction "EXT_INT_5") (pintype "input"))
    )
    (net (code "14") (name "/GPS_IN") (class "Default")
      (node (ref "Antenna") (pin "SIG") (pinfunction "SIG_SIG") (pintype "passive"))
      (node (ref "L3") (pin "2") (pinfunction "2_2") (pintype "passive"))
      (node (ref "U9") (pin "3") (pinfunction "RFIN_3") (pintype "input"))
    )
    (net (code "15") (name "/GPS_TIMEPULSE") (class "Default")
      (node (ref "G_TPLS") (pin "0") (pinfunction "0_0") (pintype "passive"))
      (node (ref "U1") (pin "32") (pinfunction "PB05_32") (pintype "bidirectional"))
      (node (ref "U3") (pin "4") (pinfunction "TimePulse_4") (pintype "output"))
    )
    (net (code "16") (name "/I2C1_SCL") (class "Default")
      (node (ref "R11") (pin "1") (pinfunction "1_1") (pintype "passive"))
      (node (ref "SCL") (pin "0") (pinfunction "0_0") (pintype "passive"))
      (node (ref "U1") (pin "33") (pinfunction "PB06_33") (pintype "bidirectional"))
      (node (ref "U3") (pin "17") (pinfunction "SCL_17") (pintype "input"))
      (node (ref "U8") (pin "8") (pinfunction "SCL_8") (pintype "input"))
    )
    (net (code "17") (name "/I2C1_SDA") (class "Default")
      (node (ref "R12") (pin "1") (pinfunction "1_1") (pintype "passive"))
      (node (ref "SDA") (pin "0") (pinfunction "0_0") (pintype "passive"))
      (node (ref "U1") (pin "34") (pinfunction "PB07_34") (pintype "bidirectional"))
      (node (ref "U3") (pin "16") (pinfunction "SDA_16") (pintype "bidirectional"))
      (node (ref "U8") (pin "7") (pinfunction "SDA_7") (pintype "bidirectional"))
    )
    (net (code "18") (name "/L1_3.3_CTRL") (class "Default")
      (node (ref "L13C") (pin "0") (pinfunction "0_0") (pintype "passive"))
      (node (ref "U1") (pin "24") (pinfunction "PA12_24") (pintype "bidirectional"))
      (node (ref "U7") (pin "5") (pinfunction "On/Off_5") (pintype "input"))
    )
    (net (code "19") (name "/L1_5.0_CTRL") (class "Default")
      (node (ref "L15C") (pin "0") (pinfunction "0_0") (pintype "passive"))
      (node (ref "U1") (pin "23") (pinfunction "PA11_23") (pintype "bidirectional"))
      (node (ref "U6") (pin "5") (pinfunction "On/Off_5") (pintype "input"))
    )
    (net (code "20") (name "/LED") (class "Default")
      (node (ref "D1") (pin "A") (pinfunction "A_A") (pintype "power_in"))
      (node (ref "U1") (pin "20") (pinfunction "PA08_20") (pintype "bidirectional"))
    )
    (net (code "21") (name "/MCU_RX_GPS_TX") (class "Default")
      (node (ref "G_TX") (pin "0") (pinfunction "0_0") (pintype "passive"))
      (node (ref "U1") (pin "22") (pinfunction "PA10_22") (pintype "bidirectional"))
      (node (ref "U3") (pin "2") (pinfunction "TxD_2") (pintype "output"))
    )
    (net (code "22") (name "/MCU_TX_GPS_RX") (class "Default")
      (node (ref "G_RX") (pin "0") (pinfunction "0_0") (pintype "passive"))
      (node (ref "U1") (pin "21") (pinfunction "PA09_21") (pintype "bidirectional"))
      (node (ref "U3") (pin "3") (pinfunction "RxD_3") (pintype "input"))
    )
    (net (code "23") (name "/NRST") (class "Default")
      (node (ref "C18") (pin "2") (pinfunction "2_2") (pintype "passive"))
      (node (ref "NRST") (pin "0") (pinfunction "0_0") (pintype "passive"))
      (node (ref "RST") (pin "2") (pinfunction "2_2") (pintype "passive"))
      (node (ref "SWD") (pin "10") (pinfunction "NRST_10") (pintype "output"))
      (node (ref "U1") (pin "4") (pinfunction "NSRT_4") (pintype "bidirectional"))
    )
    (net (code "24") (name "/OSC_IN") (class "Default")
      (node (ref "C6") (pin "2") (pinfunction "2_2") (pintype "passive"))
      (node (ref "U1") (pin "2") (pinfunction "OSC_IN/PD0_2") (pintype "input"))
      (node (ref "X1") (pin "3") (pinfunction "3_3") (pintype "passive"))
    )
    (net (code "25") (name "/OSC_OUT") (class "Default")
      (node (ref "C5") (pin "2") (pinfunction "2_2") (pintype "passive"))
      (node (ref "U1") (pin "3") (pinfunction "OSC_OUT/PD1_3") (pintype "output"))
      (node (ref "X1") (pin "1") (pinfunction "1_1") (pintype "passive"))
    )
    (net (code "26") (name "/RF_IN") (class "Default")
      (node (ref "U3") (pin "11") (pinfunction "RF_IN_11") (pintype "input"))
      (node (ref "U9") (pin "6") (pinfunction "RFout_6") (pintype "output"))
    )
    (net (code "27") (name "/SHIELD") (class "Default")
      (node (ref "J3") (pin "5") (pinfunction "5_5") (pintype "passive"))
    )
    (net (code "28") (name "/SPI1_MISO") (class "Default")
      (node (ref "J2") (pin "17") (pinfunction "17_17") (pintype "passive"))
      (node (ref "MISO") (pin "0") (pinfunction "0_0") (pintype "passive"))
      (node (ref "U1") (pin "13") (pinfunction "PA06_13") (pintype "bidirectional"))
    )
    (net (code "29") (name "/SPI1_MOSI") (class "Default")
      (node (ref "J2") (pin "18") (pinfunction "18_18") (pintype "passive"))
      (node (ref "MOSI") (pin "0") (pinfunction "0_0") (pintype "passive"))
      (node (ref "U1") (pin "14") (pinfunction "PA07_14") (pintype "bidirectional"))
    )
    (net (code "30") (name "/SPI1_NSS") (class "Default")
      (node (ref "CS") (pin "0") (pinfunction "0_0") (pintype "passive"))
      (node (ref "J2") (pin "15") (pinfunction "15_15") (pintype "passive"))
      (node (ref "U1") (pin "11") (pinfunction "PA04_11") (pintype "bidirectional"))
    )
    (net (code "31") (name "/SPI1_SCK") (class "Default")
      (node (ref "J2") (pin "16") (pinfunction "16_16") (pintype "passive"))
      (node (ref "SCK") (pin "0") (pinfunction "0_0") (pintype "passive"))
      (node (ref "U1") (pin "12") (pinfunction "PA05_12") (pintype "bidirectional"))
    )
    (net (code "32") (name "/SWCLK") (class "Default")
      (node (ref "SWD") (pin "4") (pinfunction "SWDCLK_4") (pintype "output"))
      (node (ref "U1") (pin "28") (pinfunction "PA14_28") (pintype "bidirectional"))
    )
    (net (code "33") (name "/SWDIO") (class "Default")
      (node (ref "SWD") (pin "2") (pinfunction "SWDIO_2") (pintype "bidirectional"))
      (node (ref "U1") (pin "25") (pinfunction "PA13_25") (pintype "bidirectional"))
    )
    (net (code "34") (name "/SYNC_IN") (class "Default")
      (node (ref "J2") (pin "20") (pinfunction "20_20") (pintype "passive"))
      (node (ref "SI") (pin "0") (pinfunction "0_0") (pintype "passive"))
      (node (ref "U1") (pin "29") (pinfunction "PA15_29") (pintype "bidirectional"))
    )
    (net (code "35") (name "/SYNC_OUT") (class "Default")
      (node (ref "J2") (pin "19") (pinfunction "19_19") (pintype "passive"))
      (node (ref "SO") (pin "0") (pinfunction "0_0") (pintype "passive"))
      (node (ref "U1") (pin "8") (pinfunction "PA01_8") (pintype "bidirectional"))
    )
    (net (code "36") (name "/TRACESWO") (class "Default")
      (node (ref "SWD") (pin "6") (pinfunction "SWO_6") (pintype "output"))
      (node (ref "U1") (pin "30") (pinfunction "PB03_30") (pintype "bidirectional"))
    )
    (net (code "37") (name "/USART1_DE") (class "Default")
      (node (ref "DE") (pin "0") (pinfunction "0_0") (pintype "passive"))
      (node (ref "U1") (pin "16") (pinfunction "PB01_16") (pintype "bidirectional"))
      (node (ref "U4") (pin "3") (pinfunction "DE_3") (pintype "input"))
    )
    (net (code "38") (name "/USART1_RE") (class "Default")
      (node (ref "RE") (pin "0") (pinfunction "0_0") (pintype "passive"))
      (node (ref "U1") (pin "15") (pinfunction "PB00_15") (pintype "bidirectional"))
      (node (ref "U4") (pin "2") (pinfunction "RE_2") (pintype "input"))
    )
    (net (code "39") (name "/USART1_RX") (class "Default")
      (node (ref "RX") (pin "0") (pinfunction "0_0") (pintype "passive"))
      (node (ref "U1") (pin "10") (pinfunction "PA03_10") (pintype "bidirectional"))
      (node (ref "U4") (pin "1") (pinfunction "RO_1") (pintype "output"))
    )
    (net (code "40") (name "/USART1_TX") (class "Default")
      (node (ref "TX") (pin "0") (pinfunction "0_0") (pintype "passive"))
      (node (ref "U1") (pin "9") (pinfunction "PA02_9") (pintype "bidirectional"))
      (node (ref "U4") (pin "4") (pinfunction "DI_4") (pintype "input"))
    )
    (net (code "41") (name "/VCC_RF") (class "Default")
      (node (ref "C23") (pin "2") (pinfunction "2_2") (pintype "passive"))
      (node (ref "U3") (pin "14") (pinfunction "VCC_RF_14") (pintype "power_in"))
      (node (ref "U9") (pin "1") (pinfunction "Vcc_1") (pintype "power_in"))
    )
    (net (code "42") (name "/WKUP") (class "Default")
      (node (ref "C17") (pin "2") (pinfunction "2_2") (pintype "passive"))
      (node (ref "R10") (pin "2") (pinfunction "2_2") (pintype "passive"))
      (node (ref "R9") (pin "1") (pinfunction "1_1") (pintype "passive"))
      (node (ref "U1") (pin "7") (pinfunction "PA00/WKUP_7") (pintype "bidirectional"))
      (node (ref "WKUP") (pin "0") (pinfunction "0_0") (pintype "passive"))
    )
    (net (code "43") (name "GND") (class "Default")
      (node (ref "B1") (pin "-") (pinfunction "-_-") (pintype "power_in"))
      (node (ref "C1") (pin "1") (pinfunction "1_1") (pintype "passive"))
      (node (ref "C10") (pin "1") (pinfunction "1_1") (pintype "passive"))
      (node (ref "C11") (pin "1") (pinfunction "1_1") (pintype "passive"))
      (node (ref "C12") (pin "1") (pinfunction "1_1") (pintype "passive"))
      (node (ref "C13") (pin "1") (pinfunction "1_1") (pintype "passive"))
      (node (ref "C18") (pin "1") (pinfunction "1_1") (pintype "passive"))
      (node (ref "C2") (pin "1") (pinfunction "1_1") (pintype "passive"))
      (node (ref "C20") (pin "2") (pinfunction "2_2") (pintype "passive"))
      (node (ref "C21") (pin "1") (pinfunction "1_1") (pintype "passive"))
      (node (ref "C22") (pin "1") (pinfunction "1_1") (pintype "passive"))
      (node (ref "C3") (pin "1") (pinfunction "1_1") (pintype "passive"))
      (node (ref "C4") (pin "1") (pinfunction "1_1") (pintype "passive"))
      (node (ref "C5") (pin "1") (pinfunction "1_1") (pintype "passive"))
      (node (ref "C6") (pin "1") (pinfunction "1_1") (pintype "passive"))
      (node (ref "C7") (pin "1") (pinfunction "1_1") (pintype "passive"))
      (node (ref "C8") (pin "1") (pinfunction "1_1") (pintype "passive"))
      (node (ref "C9") (pin "1") (pinfunction "1_1") (pintype "passive"))
      (node (ref "J2") (pin "1") (pinfunction "1_1") (pintype "passive"))
      (node (ref "J2") (pin "10") (pinfunction "10_10") (pintype "passive"))
      (node (ref "J2") (pin "2") (pinfunction "2_2") (pintype "passive"))
      (node (ref "J2") (pin "3") (pinfunction "3_3") (pintype "passive"))
      (node (ref "J2") (pin "4") (pinfunction "4_4") (pintype "passive"))
      (node (ref "J2") (pin "5") (pinfunction "5_5") (pintype "passive"))
      (node (ref "J2") (pin "6") (pinfunction "6_6") (pintype "passive"))
      (node (ref "J2") (pin "7") (pinfunction "7_7") (pintype "passive"))
      (node (ref "J2") (pin "8") (pinfunction "8_8") (pintype "passive"))
      (node (ref "J2") (pin "9") (pinfunction "9_9") (pintype "passive"))
      (node (ref "J3") (pin "1") (pinfunction "1_1") (pintype "passive"))
      (node (ref "R10") (pin "1") (pinfunction "1_1") (pintype "passive"))
      (node (ref "R13") (pin "2") (pinfunction "2_2") (pintype "passive"))
      (node (ref "R15") (pin "1") (pinfunction "1_1") (pintype "passive"))
      (node (ref "R16") (pin "2") (pinfunction "2_2") (pintype "passive"))
      (node (ref "R2") (pin "1") (pinfunction "1_1") (pintype "passive"))
      (node (ref "R4") (pin "1") (pinfunction "1_1") (pintype "passive"))
      (node (ref "R6") (pin "1") (pinfunction "1_1") (pintype "passive"))
      (node (ref "R8") (pin "1") (pinfunction "1_1") (pintype "passive"))
      (node (ref "RST") (pin "1") (pinfunction "1_1") (pintype "passive"))
      (node (ref "SWD") (pin "3") (pinfunction "GND_3") (pintype "passive"))
      (node (ref "SWD") (pin "5") (pinfunction "GND_5") (pintype "passive"))
      (node (ref "SWD") (pin "9") (pinfunction "GNDDET_9") (pintype "passive"))
      (node (ref "U1") (pin "18") (pinfunction "GND_1_18") (pintype "power_in"))
      (node (ref "U1") (pin "26") (pinfunction "GND_2_26") (pintype "power_in"))
      (node (ref "U1") (pin "36") (pinfunction "GND_3_36") (pintype "power_in"))
      (node (ref "U1") (pin "5") (pinfunction "GNDA_5") (pintype "power_in"))
      (node (ref "U2") (pin "2") (pinfunction "GND_2") (pintype "power_in"))
      (node (ref "U2") (pin "6") (pinfunction "GND_6") (pintype "power_in"))
      (node (ref "U2") (pin "9") (pinfunction "GND_9") (pintype "power_in"))
      (node (ref "U3") (pin "1") (pinfunction "GND_1") (pintype "power_in"))
      (node (ref "U4") (pin "5") (pinfunction "GND_5") (pintype "power_in"))
      (node (ref "U8") (pin "3") (pinfunction "GND_3") (pintype "power_in"))
      (node (ref "X1") (pin "2") (pinfunction "2_2") (pintype "power_in"))
      (node (ref "X1") (pin "4") (pinfunction "4_4") (pintype "power_in"))
    )
    (net (code "44") (name "GND_RF") (class "Default")
      (node (ref "Antenna") (pin "GND") (pinfunction "GND_GND") (pintype "passive"))
      (node (ref "C23") (pin "1") (pinfunction "1_1") (pintype "passive"))
      (node (ref "L3") (pin "1") (pinfunction "1_1") (pintype "passive"))
      (node (ref "U3") (pin "10") (pinfunction "GND_10") (pintype "power_in"))
      (node (ref "U3") (pin "12") (pinfunction "GND_12") (pintype "power_in"))
      (node (ref "U9") (pin "7") (pinfunction "GND_7") (pintype "power_in"))
    )
    (net (code "45") (name "Net-(BOOT-Pad2)") (class "Default")
      (node (ref "BOOT") (pin "2") (pinfunction "2_2") (pintype "passive"))
      (node (ref "R14") (pin "2") (pinfunction "2_2") (pintype "passive"))
    )
    (net (code "46") (name "Net-(D1-PadK)") (class "Default")
      (node (ref "D1") (pin "K") (pinfunction "K_K") (pintype "power_in"))
      (node (ref "R13") (pin "1") (pinfunction "1_1") (pintype "passive"))
    )
    (net (code "47") (name "Net-(Q1-G)") (class "Default")
      (node (ref "Q1") (pin "1") (pinfunction "G_1") (pintype "passive"))
      (node (ref "R2") (pin "2") (pinfunction "2_2") (pintype "passive"))
    )
    (net (code "48") (name "Net-(R9-Pad2)") (class "Default")
      (node (ref "R9") (pin "2") (pinfunction "2_2") (pintype "passive"))
      (node (ref "WAKE") (pin "2") (pinfunction "2_2") (pintype "passive"))
    )
    (net (code "49") (name "Net-(U5-R1{slash}C1)") (class "Default")
      (node (ref "C14") (pin "2") (pinfunction "2_2") (pintype "passive"))
      (node (ref "R3") (pin "1") (pinfunction "1_1") (pintype "passive"))
      (node (ref "U5") (pin "6") (pinfunction "R1/C1_6") (pintype "input"))
    )
    (net (code "50") (name "Net-(U5-R2)") (class "Default")
      (node (ref "R4") (pin "2") (pinfunction "2_2") (pintype "passive"))
      (node (ref "U5") (pin "1") (pinfunction "R2_1") (pintype "input"))
    )
    (net (code "51") (name "Net-(U6-R1{slash}C1)") (class "Default")
      (node (ref "C15") (pin "2") (pinfunction "2_2") (pintype "passive"))
      (node (ref "R5") (pin "1") (pinfunction "1_1") (pintype "passive"))
      (node (ref "U6") (pin "6") (pinfunction "R1/C1_6") (pintype "input"))
    )
    (net (code "52") (name "Net-(U6-R2)") (class "Default")
      (node (ref "R6") (pin "2") (pinfunction "2_2") (pintype "passive"))
      (node (ref "U6") (pin "1") (pinfunction "R2_1") (pintype "input"))
    )
    (net (code "53") (name "Net-(U7-R1{slash}C1)") (class "Default")
      (node (ref "C16") (pin "2") (pinfunction "2_2") (pintype "passive"))
      (node (ref "R7") (pin "1") (pinfunction "1_1") (pintype "passive"))
      (node (ref "U7") (pin "6") (pinfunction "R1/C1_6") (pintype "input"))
    )
    (net (code "54") (name "Net-(U7-R2)") (class "Default")
      (node (ref "R8") (pin "2") (pinfunction "2_2") (pintype "passive"))
      (node (ref "U7") (pin "1") (pinfunction "R2_1") (pintype "input"))
    )
    (net (code "55") (name "Net-(U8-CAP)") (class "Default")
      (node (ref "C20") (pin "1") (pinfunction "1_1") (pintype "passive"))
      (node (ref "U8") (pin "2") (pinfunction "CAP_2") (pintype "passive"))
    )
    (net (code "56") (name "Net-(U9-AI)") (class "Default")
      (node (ref "L2") (pin "2") (pinfunction "2_2") (pintype "passive"))
      (node (ref "U9") (pin "5") (pinfunction "AI_5") (pintype "input"))
    )
    (net (code "57") (name "Net-(U9-SO)") (class "Default")
      (node (ref "L2") (pin "1") (pinfunction "1_1") (pintype "passive"))
      (node (ref "U9") (pin "4") (pinfunction "SO_4") (pintype "output"))
    )
    (net (code "58") (name "VIN") (class "Default")
      (node (ref "J3") (pin "2") (pinfunction "2_2") (pintype "passive"))
      (node (ref "Q1") (pin "3") (pinfunction "D_3") (pintype "passive"))
      (node (ref "Vin") (pin "0") (pinfunction "0_0") (pintype "passive"))
    )
    (net (code "59") (name "unconnected-(F1-Fiducial_1mm-Pad1)") (class "Default")
      (node (ref "F1") (pin "1") (pinfunction "Fiducial_1mm_1") (pintype "passive"))
    )
    (net (code "60") (name "unconnected-(F2-Fiducial_1mm-Pad1)") (class "Default")
      (node (ref "F2") (pin "1") (pinfunction "Fiducial_1mm_1") (pintype "passive"))
    )
    (net (code "61") (name "unconnected-(F3-Fiducial_1mm-Pad1)") (class "Default")
      (node (ref "F3") (pin "1") (pinfunction "Fiducial_1mm_1") (pintype "passive"))
    )
    (net (code "62") (name "unconnected-(F4-Fiducial_1mm-Pad1)") (class "Default")
      (node (ref "F4") (pin "1") (pinfunction "Fiducial_1mm_1") (pintype "passive"))
    )
    (net (code "63") (name "unconnected-(U1B-Thermal-Pad37)") (class "Default")
      (node (ref "U1") (pin "37") (pinfunction "Thermal_37") (pintype "power_in"))
    )
    (net (code "64") (name "unconnected-(U3-RESET_N-Pad9)") (class "Default")
      (node (ref "U3") (pin "9") (pinfunction "RESET_N_9") (pintype "input"))
    )
    (net (code "65") (name "unconnected-(U3-Reserved-Pad18)") (class "Default")
      (node (ref "U3") (pin "18") (pinfunction "Reserved_18") (pintype "passive"))
    )
    (net (code "66") (name "unconnected-(U3-V_ANT-Pad15)") (class "Default")
      (node (ref "U3") (pin "15") (pinfunction "V_ANT_15") (pintype "power_in"))
    )
    (net (code "67") (name "unconnected-(U8-INT1-Pad6)") (class "Default")
      (node (ref "U8") (pin "6") (pinfunction "INT1_6") (pintype "output"))
    )
    (net (code "68") (name "unconnected-(U8-INT2-Pad5)") (class "Default")
      (node (ref "U8") (pin "5") (pinfunction "INT2_5") (pintype "output"))
    )
  )
)
